# SW.net
KiCad netlist of a schematic drawn in Altium Designer
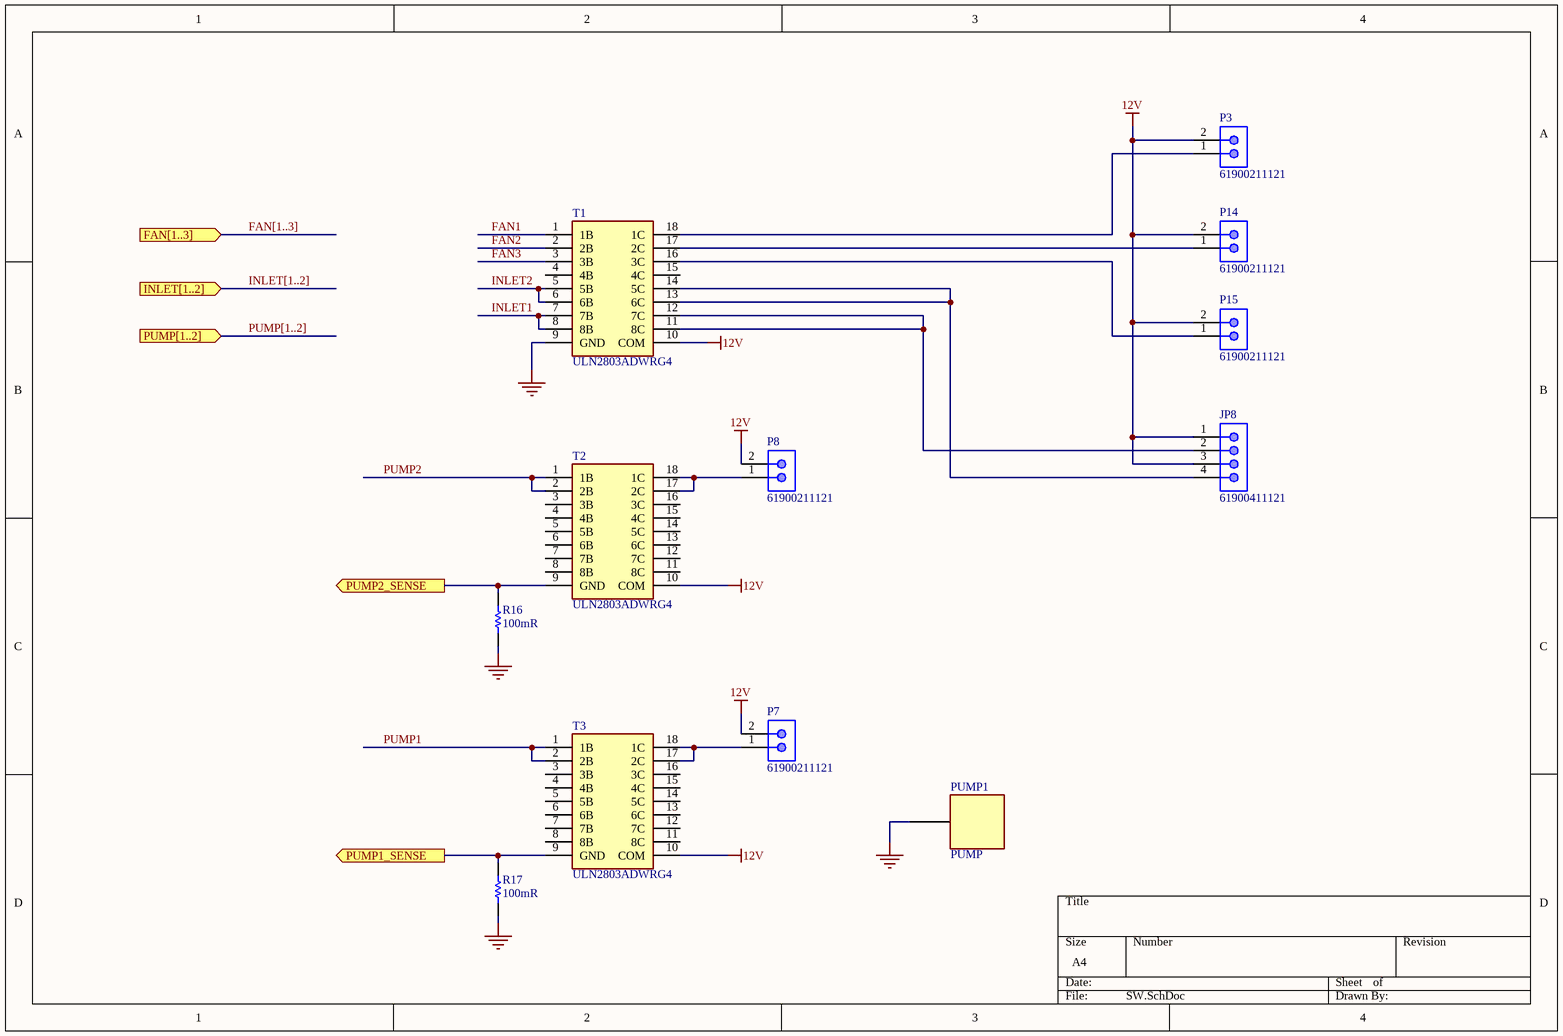
[diagram p0: SW.SchDoc]

(export (version "E")
  (design (tool "Eeschema 10.0.6"))
  (components
    (comp (ref "JP8")
      (value "61900411121")
      (footprint "61900411121")
      (description "WR-WTB THT Male Vertical Locking Header, pitch 2.54mm, 4p")
      (fields (field (name "PUBLISHER") "Wurth Elektronik"))
      (libsource (lib "Altium_WR-WTB (rev20a)") (part "61900411121"))
    )
    (comp (ref "P3")
      (value "61900211121")
      (footprint "61900211121")
      (description "WR-WTB THT Male Vertical Locking Header, pitch 2.54mm, 2p")
      (fields (field (name "PUBLISHER") "Wurth Elektronik"))
      (libsource (lib "Altium_WR-WTB (rev20a)") (part "61900211121"))
    )
    (comp (ref "P7")
      (value "61900211121")
      (footprint "61900211121")
      (description "WR-WTB THT Male Vertical Locking Header, pitch 2.54mm, 2p")
      (fields (field (name "PUBLISHER") "Wurth Elektronik"))
      (libsource (lib "Altium_WR-WTB (rev20a)") (part "61900211121"))
    )
    (comp (ref "P8")
      (value "61900211121")
      (footprint "61900211121")
      (description "WR-WTB THT Male Vertical Locking Header, pitch 2.54mm, 2p")
      (fields (field (name "PUBLISHER") "Wurth Elektronik"))
      (libsource (lib "Altium_WR-WTB (rev20a)") (part "61900211121"))
    )
    (comp (ref "P14")
      (value "61900211121")
      (footprint "61900211121")
      (description "WR-WTB THT Male Vertical Locking Header, pitch 2.54mm, 2p")
      (fields (field (name "PUBLISHER") "Wurth Elektronik"))
      (libsource (lib "Altium_WR-WTB (rev20a)") (part "61900211121"))
    )
    (comp (ref "P15")
      (value "61900211121")
      (footprint "61900211121")
      (description "WR-WTB THT Male Vertical Locking Header, pitch 2.54mm, 2p")
      (fields (field (name "PUBLISHER") "Wurth Elektronik"))
      (libsource (lib "Altium_WR-WTB (rev20a)") (part "61900211121"))
    )
    (comp (ref "PUMP1")
      (value "PUMP")
      (footprint "OpenBrewie:PUMP")
      (libsource (lib "OpenBrewie") (part "PUMP"))
    )
    (comp (ref "R16")
      (value "100mR")
      (footprint "RES_1206_H060 (_IPC_MD)")
      (description "100mR 1% 0,25W 200V 1206")
      (fields (field (name "PART NUMBER") "RES100mR1%1206"))
      (libsource (lib "MUAB_Altium_Lib") (part "RES"))
    )
    (comp (ref "R17")
      (value "100mR")
      (footprint "RES_1206_H060 (_IPC_MD)")
      (description "100mR 1% 0,25W 200V 1206")
      (fields (field (name "PART NUMBER") "RES100mR1%1206"))
      (libsource (lib "MUAB_Altium_Lib") (part "RES"))
    )
    (comp (ref "T1")
      (value "ULN2803ADWRG4")
      (footprint "OpenBrewie:SOIC127P1030X265-18N")
      (description "Darlington")
      (fields (field (name "MOUSER PART NUMBER") "595-ULN2803ADWRG4"))
      (libsource (lib "OpenBrewie") (part "ULN2803ADWRG4"))
    )
    (comp (ref "T2")
      (value "ULN2803ADWRG4")
      (footprint "OpenBrewie:SOIC127P1030X265-18N")
      (description "Darlington")
      (fields (field (name "MOUSER PART NUMBER") "595-ULN2803ADWRG4"))
      (libsource (lib "OpenBrewie") (part "ULN2803ADWRG4"))
    )
    (comp (ref "T3")
      (value "ULN2803ADWRG4")
      (footprint "OpenBrewie:SOIC127P1030X265-18N")
      (description "Darlington")
      (fields (field (name "MOUSER PART NUMBER") "595-ULN2803ADWRG4"))
      (libsource (lib "OpenBrewie") (part "ULN2803ADWRG4"))
    )
  )
  (nets
    (net (code "1") (name "/FAN1") (class "Default")
      (node (ref "T1") (pin "1") (pinfunction "1B_1") (pintype "passive"))
    )
    (net (code "2") (name "/FAN2") (class "Default")
      (node (ref "T1") (pin "2") (pinfunction "2B_2") (pintype "passive"))
    )
    (net (code "3") (name "/FAN3") (class "Default")
      (node (ref "T1") (pin "3") (pinfunction "3B_3") (pintype "passive"))
    )
    (net (code "5") (name "/INLET1") (class "Default")
      (node (ref "T1") (pin "7") (pinfunction "7B_7") (pintype "passive"))
      (node (ref "T1") (pin "8") (pinfunction "8B_8") (pintype "passive"))
    )
    (net (code "6") (name "/INLET2") (class "Default")
      (node (ref "T1") (pin "5") (pinfunction "5B_5") (pintype "passive"))
      (node (ref "T1") (pin "6") (pinfunction "6B_6") (pintype "passive"))
    )
    (net (code "8") (name "/PUMP1") (class "Default")
      (node (ref "T3") (pin "1") (pinfunction "1B_1") (pintype "passive"))
      (node (ref "T3") (pin "2") (pinfunction "2B_2") (pintype "passive"))
    )
    (net (code "9") (name "/PUMP1_SENSE") (class "Default")
      (node (ref "R17") (pin "2") (pinfunction "2_2") (pintype "passive"))
      (node (ref "T3") (pin "9") (pinfunction "GND_9") (pintype "passive"))
    )
    (net (code "10") (name "/PUMP2") (class "Default")
      (node (ref "T2") (pin "1") (pinfunction "1B_1") (pintype "passive"))
      (node (ref "T2") (pin "2") (pinfunction "2B_2") (pintype "passive"))
    )
    (net (code "11") (name "/PUMP2_SENSE") (class "Default")
      (node (ref "R16") (pin "2") (pinfunction "2_2") (pintype "passive"))
      (node (ref "T2") (pin "9") (pinfunction "GND_9") (pintype "passive"))
    )
    (net (code "13") (name "12V") (class "Default")
      (node (ref "JP8") (pin "1") (pinfunction "1_1") (pintype "passive"))
      (node (ref "JP8") (pin "3") (pinfunction "3_3") (pintype "passive"))
      (node (ref "P14") (pin "2") (pinfunction "2_2") (pintype "passive"))
      (node (ref "P15") (pin "2") (pinfunction "2_2") (pintype "passive"))
      (node (ref "P3") (pin "2") (pinfunction "2_2") (pintype "passive"))
      (node (ref "P7") (pin "2") (pinfunction "2_2") (pintype "passive"))
      (node (ref "P8") (pin "2") (pinfunction "2_2") (pintype "passive"))
      (node (ref "T1") (pin "10") (pinfunction "COM_10") (pintype "passive"))
      (node (ref "T2") (pin "10") (pinfunction "COM_10") (pintype "passive"))
      (node (ref "T3") (pin "10") (pinfunction "COM_10") (pintype "passive"))
    )
    (net (code "14") (name "GND") (class "Default")
      (node (ref "PUMP1") (pin "0") (pinfunction "CONN_0") (pintype "passive"))
      (node (ref "R16") (pin "1") (pinfunction "1_1") (pintype "passive"))
      (node (ref "R17") (pin "1") (pinfunction "1_1") (pintype "passive"))
      (node (ref "T1") (pin "9") (pinfunction "GND_9") (pintype "passive"))
    )
    (net (code "15") (name "Net-(T1-1C)") (class "Default")
      (node (ref "P3") (pin "1") (pinfunction "1_1") (pintype "passive"))
      (node (ref "T1") (pin "18") (pinfunction "1C_18") (pintype "passive"))
    )
    (net (code "16") (name "Net-(T1-2C)") (class "Default")
      (node (ref "P14") (pin "1") (pinfunction "1_1") (pintype "passive"))
      (node (ref "T1") (pin "17") (pinfunction "2C_17") (pintype "passive"))
    )
    (net (code "17") (name "Net-(T1-3C)") (class "Default")
      (node (ref "P15") (pin "1") (pinfunction "1_1") (pintype "passive"))
      (node (ref "T1") (pin "16") (pinfunction "3C_16") (pintype "passive"))
    )
    (net (code "18") (name "Net-(T1-5C)") (class "Default")
      (node (ref "JP8") (pin "4") (pinfunction "4_4") (pintype "passive"))
      (node (ref "T1") (pin "13") (pinfunction "6C_13") (pintype "passive"))
      (node (ref "T1") (pin "14") (pinfunction "5C_14") (pintype "passive"))
    )
    (net (code "19") (name "Net-(T1-7C)") (class "Default")
      (node (ref "JP8") (pin "2") (pinfunction "2_2") (pintype "passive"))
      (node (ref "T1") (pin "11") (pinfunction "8C_11") (pintype "passive"))
      (node (ref "T1") (pin "12") (pinfunction "7C_12") (pintype "passive"))
    )
    (net (code "20") (name "Net-(T2-1C)") (class "Default")
      (node (ref "P8") (pin "1") (pinfunction "1_1") (pintype "passive"))
      (node (ref "T2") (pin "17") (pinfunction "2C_17") (pintype "passive"))
      (node (ref "T2") (pin "18") (pinfunction "1C_18") (pintype "passive"))
    )
    (net (code "21") (name "Net-(T3-1C)") (class "Default")
      (node (ref "P7") (pin "1") (pinfunction "1_1") (pintype "passive"))
      (node (ref "T3") (pin "17") (pinfunction "2C_17") (pintype "passive"))
      (node (ref "T3") (pin "18") (pinfunction "1C_18") (pintype "passive"))
    )
    (net (code "22") (name "unconnected-(T1-4B-Pad4)") (class "Default")
      (node (ref "T1") (pin "4") (pinfunction "4B_4") (pintype "passive"))
    )
    (net (code "23") (name "unconnected-(T1-4C-Pad15)") (class "Default")
      (node (ref "T1") (pin "15") (pinfunction "4C_15") (pintype "passive"))
    )
    (net (code "24") (name "unconnected-(T2-3B-Pad3)") (class "Default")
      (node (ref "T2") (pin "3") (pinfunction "3B_3") (pintype "passive"))
    )
    (net (code "25") (name "unconnected-(T2-3C-Pad16)") (class "Default")
      (node (ref "T2") (pin "16") (pinfunction "3C_16") (pintype "passive"))
    )
    (net (code "26") (name "unconnected-(T2-4B-Pad4)") (class "Default")
      (node (ref "T2") (pin "4") (pinfunction "4B_4") (pintype "passive"))
    )
    (net (code "27") (name "unconnected-(T2-4C-Pad15)") (class "Default")
      (node (ref "T2") (pin "15") (pinfunction "4C_15") (pintype "passive"))
    )
    (net (code "28") (name "unconnected-(T2-5B-Pad5)") (class "Default")
      (node (ref "T2") (pin "5") (pinfunction "5B_5") (pintype "passive"))
    )
    (net (code "29") (name "unconnected-(T2-5C-Pad14)") (class "Default")
      (node (ref "T2") (pin "14") (pinfunction "5C_14") (pintype "passive"))
    )
    (net (code "30") (name "unconnected-(T2-6B-Pad6)") (class "Default")
      (node (ref "T2") (pin "6") (pinfunction "6B_6") (pintype "passive"))
    )
    (net (code "31") (name "unconnected-(T2-6C-Pad13)") (class "Default")
      (node (ref "T2") (pin "13") (pinfunction "6C_13") (pintype "passive"))
    )
    (net (code "32") (name "unconnected-(T2-7B-Pad7)") (class "Default")
      (node (ref "T2") (pin "7") (pinfunction "7B_7") (pintype "passive"))
    )
    (net (code "33") (name "unconnected-(T2-7C-Pad12)") (class "Default")
      (node (ref "T2") (pin "12") (pinfunction "7C_12") (pintype "passive"))
    )
    (net (code "34") (name "unconnected-(T2-8B-Pad8)") (class "Default")
      (node (ref "T2") (pin "8") (pinfunction "8B_8") (pintype "passive"))
    )
    (net (code "35") (name "unconnected-(T2-8C-Pad11)") (class "Default")
      (node (ref "T2") (pin "11") (pinfunction "8C_11") (pintype "passive"))
    )
    (net (code "36") (name "unconnected-(T3-3B-Pad3)") (class "Default")
      (node (ref "T3") (pin "3") (pinfunction "3B_3") (pintype "passive"))
    )
    (net (code "37") (name "unconnected-(T3-3C-Pad16)") (class "Default")
      (node (ref "T3") (pin "16") (pinfunction "3C_16") (pintype "passive"))
    )
    (net (code "38") (name "unconnected-(T3-4B-Pad4)") (class "Default")
      (node (ref "T3") (pin "4") (pinfunction "4B_4") (pintype "passive"))
    )
    (net (code "39") (name "unconnected-(T3-4C-Pad15)") (class "Default")
      (node (ref "T3") (pin "15") (pinfunction "4C_15") (pintype "passive"))
    )
    (net (code "40") (name "unconnected-(T3-5B-Pad5)") (class "Default")
      (node (ref "T3") (pin "5") (pinfunction "5B_5") (pintype "passive"))
    )
    (net (code "41") (name "unconnected-(T3-5C-Pad14)") (class "Default")
      (node (ref "T3") (pin "14") (pinfunction "5C_14") (pintype "passive"))
    )
    (net (code "42") (name "unconnected-(T3-6B-Pad6)") (class "Default")
      (node (ref "T3") (pin "6") (pinfunction "6B_6") (pintype "passive"))
    )
    (net (code "43") (name "unconnected-(T3-6C-Pad13)") (class "Default")
      (node (ref "T3") (pin "13") (pinfunction "6C_13") (pintype "passive"))
    )
    (net (code "44") (name "unconnected-(T3-7B-Pad7)") (class "Default")
      (node (ref "T3") (pin "7") (pinfunction "7B_7") (pintype "passive"))
    )
    (net (code "45") (name "unconnected-(T3-7C-Pad12)") (class "Default")
      (node (ref "T3") (pin "12") (pinfunction "7C_12") (pintype "passive"))
    )
    (net (code "46") (name "unconnected-(T3-8B-Pad8)") (class "Default")
      (node (ref "T3") (pin "8") (pinfunction "8B_8") (pintype "passive"))
    )
    (net (code "47") (name "unconnected-(T3-8C-Pad11)") (class "Default")
      (node (ref "T3") (pin "11") (pinfunction "8C_11") (pintype "passive"))
    )
  )
)
